# ESPWriter.net
KiCad netlist of a schematic drawn in EAGLE
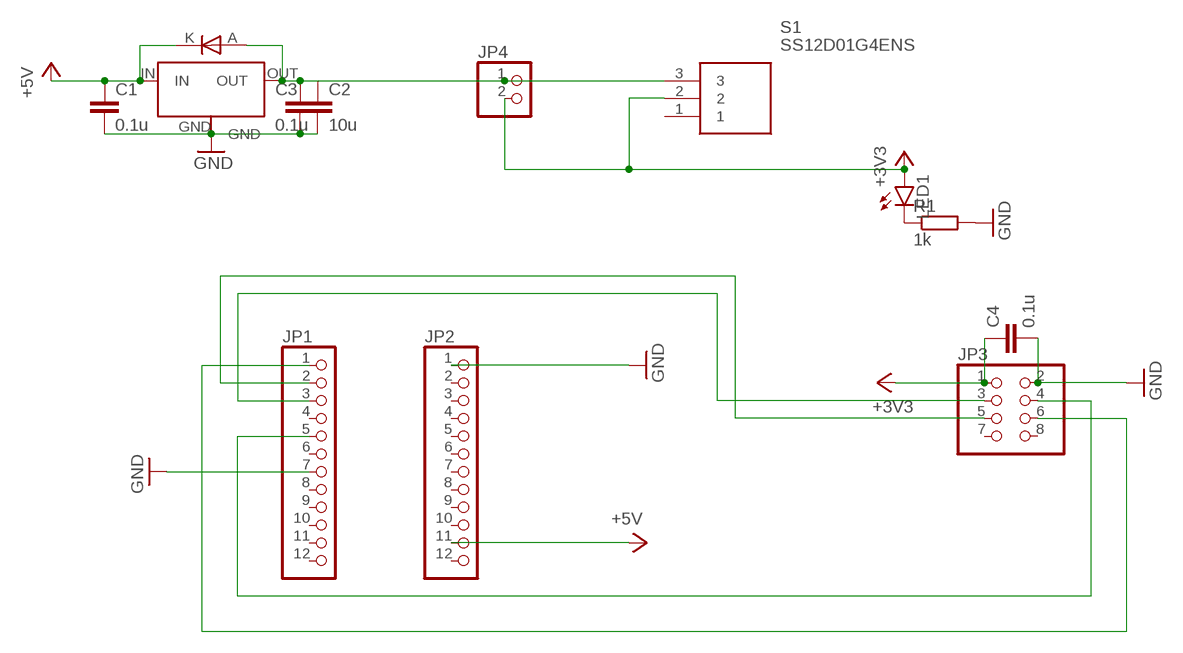
[diagram p0: schematic, sheet 1]

(export (version "E")
  (design (tool "Eeschema 10.0.6"))
  (components
    (comp (ref "C1")
      (value "0.1u")
      (footprint "eagle-import:C0603")
      (libsource (lib "eagle-import") (part "C-EUC0603"))
    )
    (comp (ref "C2")
      (value "10u")
      (footprint "eagle-import:C0603")
      (libsource (lib "eagle-import") (part "C-EUC0603"))
    )
    (comp (ref "C3")
      (value "0.1u")
      (footprint "eagle-import:C0603")
      (libsource (lib "eagle-import") (part "C-EUC0603"))
    )
    (comp (ref "C4")
      (value "0.1u")
      (footprint "eagle-import:C0603")
      (libsource (lib "eagle-import") (part "C-EUC0603"))
    )
    (comp (ref "JP1")
      (value "PINHD-1X12")
      (footprint "eagle-import:1X12")
      (libsource (lib "eagle-import") (part "PINHD-1X12"))
    )
    (comp (ref "JP2")
      (value "PINHD-1X12")
      (footprint "eagle-import:1X12")
      (libsource (lib "eagle-import") (part "PINHD-1X12"))
    )
    (comp (ref "JP3")
      (value "PINHD-2X4")
      (footprint "eagle-import:2X04")
      (libsource (lib "eagle-import") (part "PINHD-2X4"))
    )
    (comp (ref "JP4")
      (value "PINHD-1X2")
      (footprint "eagle-import:1X02")
      (libsource (lib "eagle-import") (part "PINHD-1X2"))
    )
    (comp (ref "LED1")
      (value "LEDCHIPLED_0603")
      (footprint "eagle-import:CHIPLED_0603")
      (libsource (lib "eagle-import") (part "LEDCHIPLED_0603"))
    )
    (comp (ref "R1")
      (value "1k")
      (footprint "eagle-import:R0603")
      (libsource (lib "eagle-import") (part "R-EU_R0603"))
    )
    (comp (ref "S1")
      (value "SS12D01G4ENS")
      (footprint "eagle-import:SS12D01G4")
      (fields (field (name "MOUSER_PART_NUMBER") "611-SS12D01G4ENS"))
      (libsource (lib "eagle-import") (part "SS12D01G4ENS"))
    )
    (comp (ref "U$5")
      (value "3v3 reg")
      (footprint "eagle-import:NJM2391DL1-33")
      (libsource (lib "eagle-import") (part "NJM2391DL1-33"))
    )
    (comp (ref "U$6")
      (value "SS2040FL")
      (footprint "eagle-import:SS2040FL")
      (libsource (lib "eagle-import") (part "SS2040FL"))
    )
  )
  (nets
    (net (code "1") (name "+3V3") (class "Default")
      (node (ref "C4") (pin "1") (pinfunction "1_1") (pintype "passive"))
      (node (ref "JP3") (pin "1") (pinfunction "1_1") (pintype "passive"))
      (node (ref "JP4") (pin "2") (pinfunction "2_2") (pintype "passive"))
      (node (ref "LED1") (pin "A") (pinfunction "A_A") (pintype "passive"))
      (node (ref "S1") (pin "2") (pinfunction "2_2") (pintype "bidirectional"))
    )
    (net (code "2") (name "+5V") (class "Default")
      (node (ref "C1") (pin "1") (pinfunction "1_1") (pintype "passive"))
      (node (ref "JP2") (pin "11") (pinfunction "11_11") (pintype "passive"))
      (node (ref "U$5") (pin "IN") (pinfunction "IN_IN") (pintype "bidirectional"))
      (node (ref "U$6") (pin "K") (pinfunction "K_K") (pintype "bidirectional"))
    )
    (net (code "3") (name "GND") (class "Default")
      (node (ref "C1") (pin "2") (pinfunction "2_2") (pintype "passive"))
      (node (ref "C2") (pin "2") (pinfunction "2_2") (pintype "passive"))
      (node (ref "C3") (pin "2") (pinfunction "2_2") (pintype "passive"))
      (node (ref "C4") (pin "2") (pinfunction "2_2") (pintype "passive"))
      (node (ref "JP1") (pin "7") (pinfunction "7_7") (pintype "passive"))
      (node (ref "JP2") (pin "1") (pinfunction "1_1") (pintype "passive"))
      (node (ref "JP3") (pin "2") (pinfunction "2_2") (pintype "passive"))
      (node (ref "R1") (pin "2") (pinfunction "2_2") (pintype "passive"))
      (node (ref "U$5") (pin "GND") (pinfunction "GND_GND") (pintype "bidirectional"))
    )
    (net (code "4") (name "Net-(C2-Pad1)") (class "Default")
      (node (ref "C2") (pin "1") (pinfunction "1_1") (pintype "passive"))
      (node (ref "C3") (pin "1") (pinfunction "1_1") (pintype "passive"))
      (node (ref "JP4") (pin "1") (pinfunction "1_1") (pintype "passive"))
      (node (ref "S1") (pin "3") (pinfunction "3_3") (pintype "bidirectional"))
      (node (ref "U$5") (pin "OUT") (pinfunction "OUT_OUT") (pintype "bidirectional"))
      (node (ref "U$6") (pin "A") (pinfunction "A_A") (pintype "bidirectional"))
    )
    (net (code "5") (name "Net-(JP1-Pad1)") (class "Default")
      (node (ref "JP1") (pin "1") (pinfunction "1_1") (pintype "passive"))
      (node (ref "JP3") (pin "6") (pinfunction "6_6") (pintype "passive"))
    )
    (net (code "6") (name "Net-(JP1-Pad2)") (class "Default")
      (node (ref "JP1") (pin "2") (pinfunction "2_2") (pintype "passive"))
      (node (ref "JP3") (pin "5") (pinfunction "5_5") (pintype "passive"))
    )
    (net (code "7") (name "Net-(JP1-Pad3)") (class "Default")
      (node (ref "JP1") (pin "3") (pinfunction "3_3") (pintype "passive"))
      (node (ref "JP3") (pin "3") (pinfunction "3_3") (pintype "passive"))
    )
    (net (code "8") (name "Net-(JP1-Pad5)") (class "Default")
      (node (ref "JP1") (pin "5") (pinfunction "5_5") (pintype "passive"))
      (node (ref "JP3") (pin "4") (pinfunction "4_4") (pintype "passive"))
    )
    (net (code "9") (name "Net-(LED1-PadC)") (class "Default")
      (node (ref "LED1") (pin "C") (pinfunction "C_C") (pintype "passive"))
      (node (ref "R1") (pin "1") (pinfunction "1_1") (pintype "passive"))
    )
    (net (code "10") (name "unconnected-(JP1-Pad4)") (class "Default")
      (node (ref "JP1") (pin "4") (pinfunction "4_4") (pintype "passive"))
    )
    (net (code "11") (name "unconnected-(JP1-Pad6)") (class "Default")
      (node (ref "JP1") (pin "6") (pinfunction "6_6") (pintype "passive"))
    )
    (net (code "12") (name "unconnected-(JP1-Pad8)") (class "Default")
      (node (ref "JP1") (pin "8") (pinfunction "8_8") (pintype "passive"))
    )
    (net (code "13") (name "unconnected-(JP1-Pad9)") (class "Default")
      (node (ref "JP1") (pin "9") (pinfunction "9_9") (pintype "passive"))
    )
    (net (code "14") (name "unconnected-(JP1-Pad10)") (class "Default")
      (node (ref "JP1") (pin "10") (pinfunction "10_10") (pintype "passive"))
    )
    (net (code "15") (name "unconnected-(JP1-Pad11)") (class "Default")
      (node (ref "JP1") (pin "11") (pinfunction "11_11") (pintype "passive"))
    )
    (net (code "16") (name "unconnected-(JP1-Pad12)") (class "Default")
      (node (ref "JP1") (pin "12") (pinfunction "12_12") (pintype "passive"))
    )
    (net (code "17") (name "unconnected-(JP2-Pad2)") (class "Default")
      (node (ref "JP2") (pin "2") (pinfunction "2_2") (pintype "passive"))
    )
    (net (code "18") (name "unconnected-(JP2-Pad3)") (class "Default")
      (node (ref "JP2") (pin "3") (pinfunction "3_3") (pintype "passive"))
    )
    (net (code "19") (name "unconnected-(JP2-Pad4)") (class "Default")
      (node (ref "JP2") (pin "4") (pinfunction "4_4") (pintype "passive"))
    )
    (net (code "20") (name "unconnected-(JP2-Pad5)") (class "Default")
      (node (ref "JP2") (pin "5") (pinfunction "5_5") (pintype "passive"))
    )
    (net (code "21") (name "unconnected-(JP2-Pad6)") (class "Default")
      (node (ref "JP2") (pin "6") (pinfunction "6_6") (pintype "passive"))
    )
    (net (code "22") (name "unconnected-(JP2-Pad7)") (class "Default")
      (node (ref "JP2") (pin "7") (pinfunction "7_7") (pintype "passive"))
    )
    (net (code "23") (name "unconnected-(JP2-Pad8)") (class "Default")
      (node (ref "JP2") (pin "8") (pinfunction "8_8") (pintype "passive"))
    )
    (net (code "24") (name "unconnected-(JP2-Pad9)") (class "Default")
      (node (ref "JP2") (pin "9") (pinfunction "9_9") (pintype "passive"))
    )
    (net (code "25") (name "unconnected-(JP2-Pad10)") (class "Default")
      (node (ref "JP2") (pin "10") (pinfunction "10_10") (pintype "passive"))
    )
    (net (code "26") (name "unconnected-(JP2-Pad12)") (class "Default")
      (node (ref "JP2") (pin "12") (pinfunction "12_12") (pintype "passive"))
    )
    (net (code "27") (name "unconnected-(JP3-Pad7)") (class "Default")
      (node (ref "JP3") (pin "7") (pinfunction "7_7") (pintype "passive"))
    )
    (net (code "28") (name "unconnected-(JP3-Pad8)") (class "Default")
      (node (ref "JP3") (pin "8") (pinfunction "8_8") (pintype "passive"))
    )
    (net (code "29") (name "unconnected-(S1-Pad1)") (class "Default")
      (node (ref "S1") (pin "1") (pinfunction "1_1") (pintype "bidirectional"))
    )
  )
)
